# working.net
KiCad netlist of a schematic drawn in EAGLE
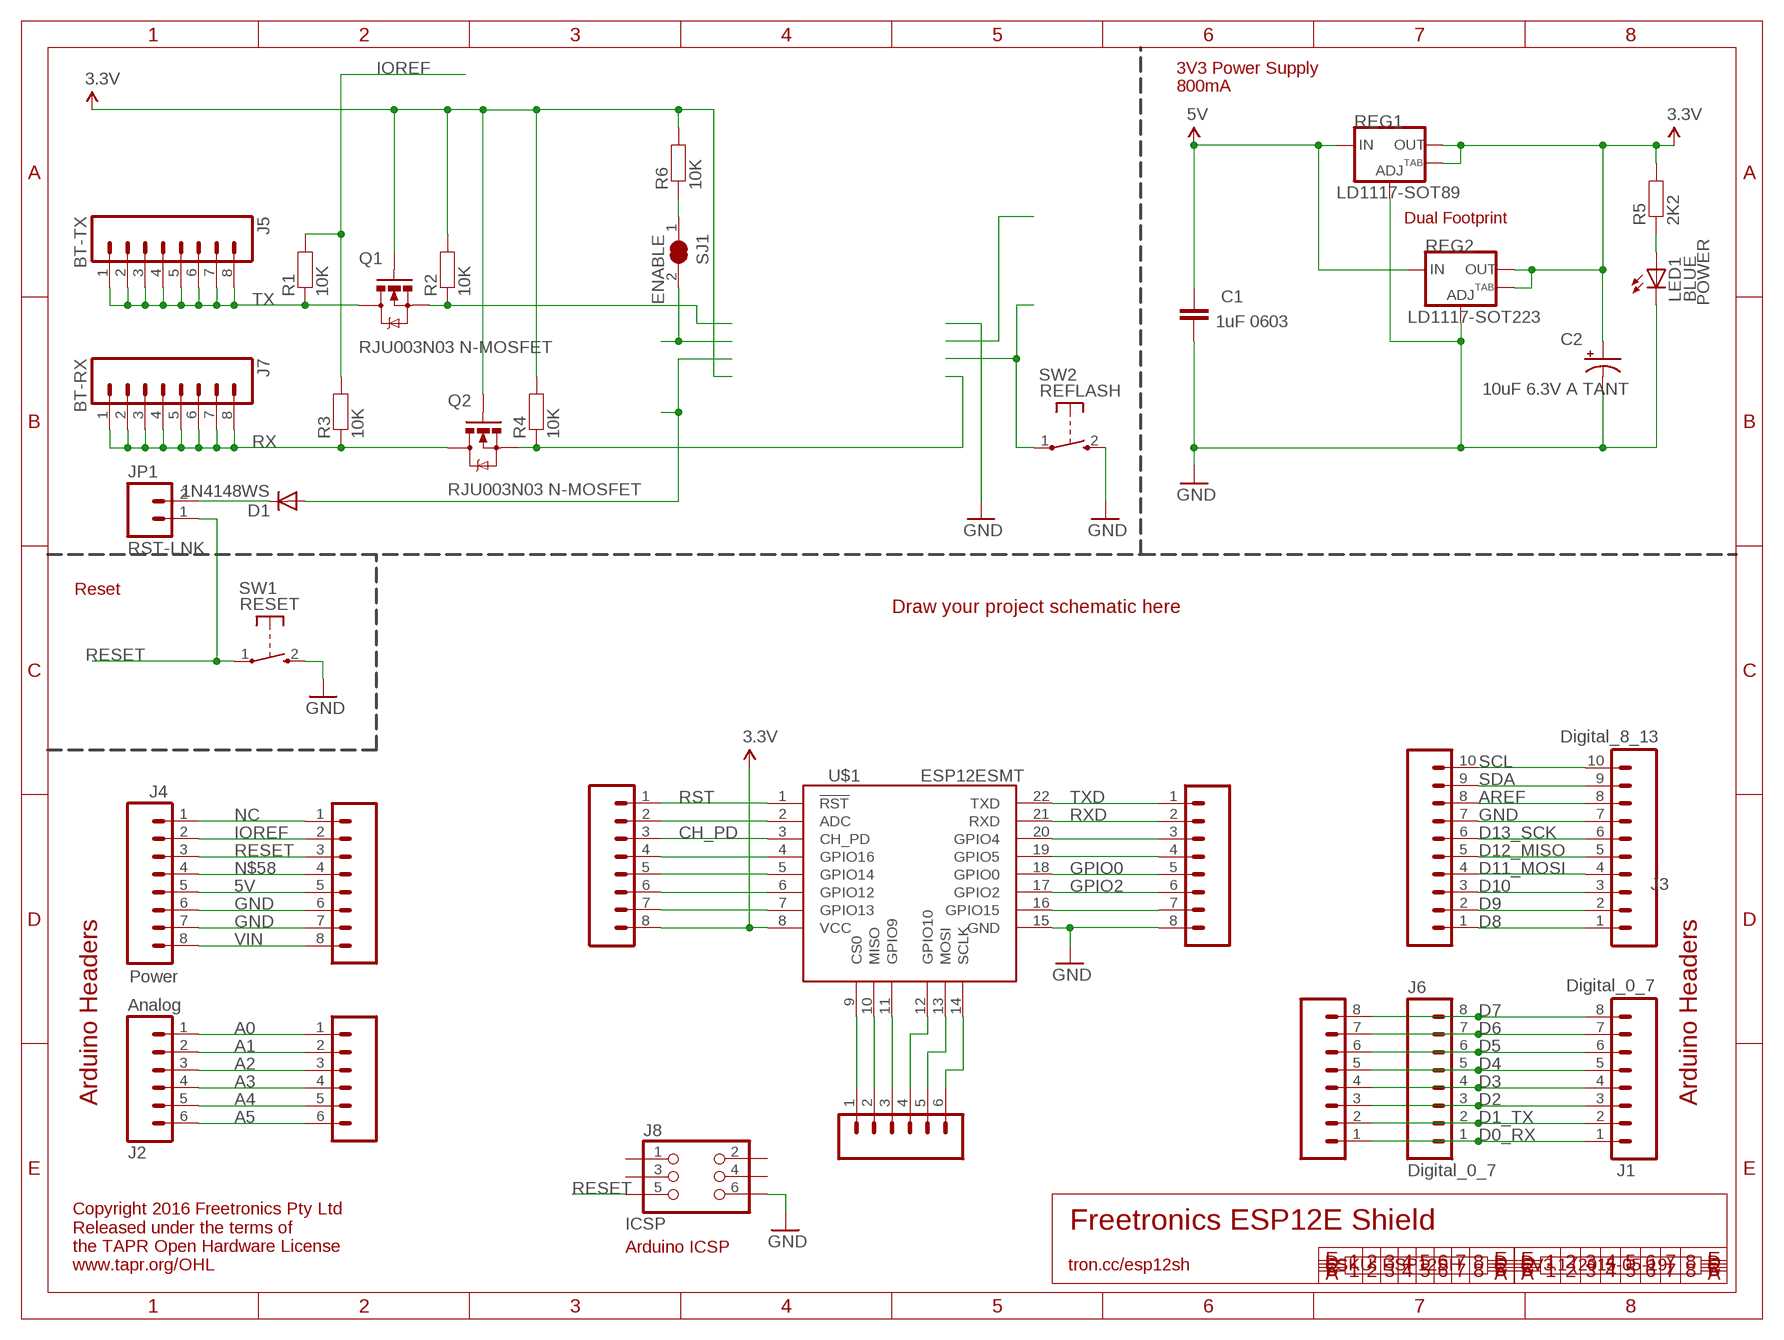
[diagram p0: schematic, sheet 1]

(export (version "E")
  (design (tool "Eeschema 10.0.6"))
  (components
    (comp (ref "C1")
      (value "1uF 0603")
      (footprint "eagle-import:0603")
      (libsource (lib "eagle-import") (part "CAP0603"))
    )
    (comp (ref "C2")
      (value "10uF 6.3V A TANT")
      (footprint "eagle-import:EIA3216")
      (libsource (lib "eagle-import") (part "CAP_POL1206"))
    )
    (comp (ref "D1")
      (value "1N4148WS")
      (footprint "eagle-import:SOD-323")
      (libsource (lib "eagle-import") (part "DIODESOD"))
    )
    (comp (ref "J1")
      (value "Digital_0_7")
      (footprint "eagle-import:1X08")
      (libsource (lib "eagle-import") (part "M08"))
    )
    (comp (ref "J2")
      (value "Analog")
      (footprint "eagle-import:1X06")
      (libsource (lib "eagle-import") (part "M06SIP"))
    )
    (comp (ref "J3")
      (value "Digital_8_13")
      (footprint "eagle-import:1X10")
      (libsource (lib "eagle-import") (part "M100.1"))
    )
    (comp (ref "J4")
      (value "Power")
      (footprint "eagle-import:1X08")
      (libsource (lib "eagle-import") (part "M08"))
    )
    (comp (ref "J5")
      (value "BT-TX")
      (footprint "eagle-import:1X08")
      (libsource (lib "eagle-import") (part "freetronics-original_M08"))
    )
    (comp (ref "J6")
      (value "Digital_0_7")
      (footprint "eagle-import:1X08")
      (libsource (lib "eagle-import") (part "freetronics-original_M08"))
    )
    (comp (ref "J7")
      (value "BT-RX")
      (footprint "eagle-import:1X08")
      (libsource (lib "eagle-import") (part "freetronics-original_M08"))
    )
    (comp (ref "J8")
      (value "ICSP")
      (footprint "eagle-import:2X03PTH")
      (libsource (lib "eagle-import") (part "ICSPPTH"))
    )
    (comp (ref "JP1")
      (value "RST-LNK")
      (footprint "eagle-import:1X02")
      (libsource (lib "eagle-import") (part "M02PTH"))
    )
    (comp (ref "LED1")
      (value "BLUE")
      (footprint "eagle-import:LED-0603")
      (libsource (lib "eagle-import") (part "LED0603"))
    )
    (comp (ref "Q1")
      (value "RJU003N03 N-MOSFET")
      (footprint "eagle-import:SOT32-3")
      (libsource (lib "eagle-import") (part "MOSFET-NSOT-323"))
    )
    (comp (ref "Q2")
      (value "RJU003N03 N-MOSFET")
      (footprint "eagle-import:SOT32-3")
      (libsource (lib "eagle-import") (part "MOSFET-NSOT-323"))
    )
    (comp (ref "R1")
      (value "10K")
      (footprint "eagle-import:0603")
      (libsource (lib "eagle-import") (part "RESISTOR0603"))
    )
    (comp (ref "R2")
      (value "10K")
      (footprint "eagle-import:0603")
      (libsource (lib "eagle-import") (part "RESISTOR0603"))
    )
    (comp (ref "R3")
      (value "10K")
      (footprint "eagle-import:0603")
      (libsource (lib "eagle-import") (part "RESISTOR0603"))
    )
    (comp (ref "R4")
      (value "10K")
      (footprint "eagle-import:0603")
      (libsource (lib "eagle-import") (part "RESISTOR0603"))
    )
    (comp (ref "R5")
      (value "2K2")
      (footprint "eagle-import:0603")
      (libsource (lib "eagle-import") (part "RESISTOR0603"))
    )
    (comp (ref "R6")
      (value "10K")
      (footprint "eagle-import:0603")
      (libsource (lib "eagle-import") (part "RESISTOR0603"))
    )
    (comp (ref "REG1")
      (value "LD1117-SOT89")
      (footprint "eagle-import:SOT89")
      (libsource (lib "eagle-import") (part "V_REG_LM1117SOT89"))
    )
    (comp (ref "REG2")
      (value "LD1117-SOT223")
      (footprint "eagle-import:SOT223")
      (libsource (lib "eagle-import") (part "V_REG_LM1117SOT223"))
    )
    (comp (ref "SJ1")
      (value "ENABLE")
      (footprint "eagle-import:SJC")
      (libsource (lib "eagle-import") (part "SJCN"))
    )
    (comp (ref "SL1")
      (value "Digital_0_7")
      (footprint "eagle-import:1X08")
      (libsource (lib "eagle-import") (part "M08"))
    )
    (comp (ref "SL2")
      (value "Analog")
      (footprint "eagle-import:1X06")
      (libsource (lib "eagle-import") (part "M06SIP"))
    )
    (comp (ref "SL3")
      (value "Digital_8_13")
      (footprint "eagle-import:1X10")
      (libsource (lib "eagle-import") (part "M100.1"))
    )
    (comp (ref "SL4")
      (value "Power")
      (footprint "eagle-import:1X08")
      (libsource (lib "eagle-import") (part "M08"))
    )
    (comp (ref "SL5")
      (value "5V")
      (footprint "eagle-import:1X08")
      (libsource (lib "eagle-import") (part "M08"))
    )
    (comp (ref "SL6")
      (value "5V")
      (footprint "eagle-import:1X08")
      (libsource (lib "eagle-import") (part "M08"))
    )
    (comp (ref "SL7")
      (value "Analog")
      (footprint "eagle-import:1X06")
      (libsource (lib "eagle-import") (part "M06SIP"))
    )
    (comp (ref "SW1")
      (value "RESET")
      (footprint "eagle-import:TACTILE_SWITCH_SMD_2PIN_TINY")
      (libsource (lib "eagle-import") (part "TAC_SWITCH_2PIN"))
    )
    (comp (ref "SW2")
      (value "REFLASH")
      (footprint "eagle-import:TACTILE_SWITCH_SMD_2PIN_TINY")
      (libsource (lib "eagle-import") (part "TAC_SWITCH_2PIN"))
    )
    (comp (ref "U$1")
      (value "ESP12ESMT")
      (footprint "eagle-import:ESP12E")
      (libsource (lib "eagle-import") (part "ESP12ESMT"))
    )
  )
  (nets
    (net (code "1") (name "/A0") (class "Default")
      (node (ref "J2") (pin "1") (pinfunction "1_1") (pintype "passive"))
      (node (ref "SL2") (pin "1") (pinfunction "1_1") (pintype "passive"))
    )
    (net (code "2") (name "/A1") (class "Default")
      (node (ref "J2") (pin "2") (pinfunction "2_2") (pintype "passive"))
      (node (ref "SL2") (pin "2") (pinfunction "2_2") (pintype "passive"))
    )
    (net (code "3") (name "/A2") (class "Default")
      (node (ref "J2") (pin "3") (pinfunction "3_3") (pintype "passive"))
      (node (ref "SL2") (pin "3") (pinfunction "3_3") (pintype "passive"))
    )
    (net (code "4") (name "/A3") (class "Default")
      (node (ref "J2") (pin "4") (pinfunction "4_4") (pintype "passive"))
      (node (ref "SL2") (pin "4") (pinfunction "4_4") (pintype "passive"))
    )
    (net (code "5") (name "/A4") (class "Default")
      (node (ref "J2") (pin "5") (pinfunction "5_5") (pintype "passive"))
      (node (ref "SL2") (pin "5") (pinfunction "5_5") (pintype "passive"))
    )
    (net (code "6") (name "/A5") (class "Default")
      (node (ref "J2") (pin "6") (pinfunction "6_6") (pintype "passive"))
      (node (ref "SL2") (pin "6") (pinfunction "6_6") (pintype "passive"))
    )
    (net (code "7") (name "/AREF") (class "Default")
      (node (ref "J3") (pin "8") (pinfunction "8_8") (pintype "passive"))
      (node (ref "SL3") (pin "8") (pinfunction "8_8") (pintype "passive"))
    )
    (net (code "8") (name "/CH_PD") (class "Default")
      (node (ref "SJ1") (pin "2") (pinfunction "2_2") (pintype "passive"))
      (node (ref "SL6") (pin "3") (pinfunction "3_3") (pintype "passive"))
      (node (ref "U$1") (pin "3") (pinfunction "CH_PD_3") (pintype "input"))
    )
    (net (code "9") (name "/D0_RX") (class "Default")
      (node (ref "J1") (pin "1") (pinfunction "1_1") (pintype "passive"))
      (node (ref "J6") (pin "1") (pinfunction "1_1") (pintype "passive"))
      (node (ref "SL1") (pin "1") (pinfunction "1_1") (pintype "passive"))
    )
    (net (code "10") (name "/D1_TX") (class "Default")
      (node (ref "J1") (pin "2") (pinfunction "2_2") (pintype "passive"))
      (node (ref "J6") (pin "2") (pinfunction "2_2") (pintype "passive"))
      (node (ref "SL1") (pin "2") (pinfunction "2_2") (pintype "passive"))
    )
    (net (code "11") (name "/D2") (class "Default")
      (node (ref "J1") (pin "3") (pinfunction "3_3") (pintype "passive"))
      (node (ref "J6") (pin "3") (pinfunction "3_3") (pintype "passive"))
      (node (ref "SL1") (pin "3") (pinfunction "3_3") (pintype "passive"))
    )
    (net (code "12") (name "/D3") (class "Default")
      (node (ref "J1") (pin "4") (pinfunction "4_4") (pintype "passive"))
      (node (ref "J6") (pin "4") (pinfunction "4_4") (pintype "passive"))
      (node (ref "SL1") (pin "4") (pinfunction "4_4") (pintype "passive"))
    )
    (net (code "13") (name "/D4") (class "Default")
      (node (ref "J1") (pin "5") (pinfunction "5_5") (pintype "passive"))
      (node (ref "J6") (pin "5") (pinfunction "5_5") (pintype "passive"))
      (node (ref "SL1") (pin "5") (pinfunction "5_5") (pintype "passive"))
    )
    (net (code "14") (name "/D5") (class "Default")
      (node (ref "J1") (pin "6") (pinfunction "6_6") (pintype "passive"))
      (node (ref "J6") (pin "6") (pinfunction "6_6") (pintype "passive"))
      (node (ref "SL1") (pin "6") (pinfunction "6_6") (pintype "passive"))
    )
    (net (code "15") (name "/D6") (class "Default")
      (node (ref "J1") (pin "7") (pinfunction "7_7") (pintype "passive"))
      (node (ref "J6") (pin "7") (pinfunction "7_7") (pintype "passive"))
      (node (ref "SL1") (pin "7") (pinfunction "7_7") (pintype "passive"))
    )
    (net (code "16") (name "/D7") (class "Default")
      (node (ref "J1") (pin "8") (pinfunction "8_8") (pintype "passive"))
      (node (ref "J6") (pin "8") (pinfunction "8_8") (pintype "passive"))
      (node (ref "SL1") (pin "8") (pinfunction "8_8") (pintype "passive"))
    )
    (net (code "17") (name "/D8") (class "Default")
      (node (ref "J3") (pin "1") (pinfunction "1_1") (pintype "passive"))
      (node (ref "SL3") (pin "1") (pinfunction "1_1") (pintype "passive"))
    )
    (net (code "18") (name "/D9") (class "Default")
      (node (ref "J3") (pin "2") (pinfunction "2_2") (pintype "passive"))
      (node (ref "SL3") (pin "2") (pinfunction "2_2") (pintype "passive"))
    )
    (net (code "19") (name "/D10") (class "Default")
      (node (ref "J3") (pin "3") (pinfunction "3_3") (pintype "passive"))
      (node (ref "SL3") (pin "3") (pinfunction "3_3") (pintype "passive"))
    )
    (net (code "20") (name "/D11_MOSI") (class "Default")
      (node (ref "J3") (pin "4") (pinfunction "4_4") (pintype "passive"))
      (node (ref "SL3") (pin "4") (pinfunction "4_4") (pintype "passive"))
    )
    (net (code "21") (name "/D12_MISO") (class "Default")
      (node (ref "J3") (pin "5") (pinfunction "5_5") (pintype "passive"))
      (node (ref "SL3") (pin "5") (pinfunction "5_5") (pintype "passive"))
    )
    (net (code "22") (name "/D13_SCK") (class "Default")
      (node (ref "J3") (pin "6") (pinfunction "6_6") (pintype "passive"))
      (node (ref "SL3") (pin "6") (pinfunction "6_6") (pintype "passive"))
    )
    (net (code "23") (name "/GPIO0") (class "Default")
      (node (ref "SL5") (pin "5") (pinfunction "5_5") (pintype "passive"))
      (node (ref "SW2") (pin "1") (pinfunction "P_1") (pintype "passive"))
      (node (ref "U$1") (pin "18") (pinfunction "GPIO0_18") (pintype "bidirectional"))
    )
    (net (code "24") (name "/GPIO2") (class "Default")
      (node (ref "SL5") (pin "6") (pinfunction "6_6") (pintype "passive"))
      (node (ref "U$1") (pin "17") (pinfunction "GPIO2_17") (pintype "bidirectional"))
    )
    (net (code "25") (name "/IOREF") (class "Default")
      (node (ref "J4") (pin "2") (pinfunction "2_2") (pintype "passive"))
      (node (ref "R1") (pin "2") (pinfunction "2_2") (pintype "passive"))
      (node (ref "R3") (pin "2") (pinfunction "2_2") (pintype "passive"))
      (node (ref "SL4") (pin "2") (pinfunction "2_2") (pintype "passive"))
    )
    (net (code "26") (name "/N$58") (class "Default")
      (node (ref "J4") (pin "4") (pinfunction "4_4") (pintype "passive"))
      (node (ref "SL4") (pin "4") (pinfunction "4_4") (pintype "passive"))
    )
    (net (code "27") (name "/NC") (class "Default")
      (node (ref "J4") (pin "1") (pinfunction "1_1") (pintype "passive"))
      (node (ref "SL4") (pin "1") (pinfunction "1_1") (pintype "passive"))
    )
    (net (code "28") (name "/RESET") (class "Default")
      (node (ref "J4") (pin "3") (pinfunction "3_3") (pintype "passive"))
      (node (ref "J8") (pin "5") (pinfunction "5_5") (pintype "passive"))
      (node (ref "JP1") (pin "1") (pinfunction "1_1") (pintype "passive"))
      (node (ref "SL4") (pin "3") (pinfunction "3_3") (pintype "passive"))
      (node (ref "SW1") (pin "1") (pinfunction "P_1") (pintype "passive"))
    )
    (net (code "29") (name "/RST") (class "Default")
      (node (ref "D1") (pin "2") (pinfunction "A_2") (pintype "passive"))
      (node (ref "SL6") (pin "1") (pinfunction "1_1") (pintype "passive"))
      (node (ref "U$1") (pin "1") (pinfunction "~{RST}_1") (pintype "bidirectional"))
    )
    (net (code "30") (name "/RX") (class "Default")
      (node (ref "J7") (pin "1") (pinfunction "1_1") (pintype "passive"))
      (node (ref "J7") (pin "2") (pinfunction "2_2") (pintype "passive"))
      (node (ref "J7") (pin "3") (pinfunction "3_3") (pintype "passive"))
      (node (ref "J7") (pin "4") (pinfunction "4_4") (pintype "passive"))
      (node (ref "J7") (pin "5") (pinfunction "5_5") (pintype "passive"))
      (node (ref "J7") (pin "6") (pinfunction "6_6") (pintype "passive"))
      (node (ref "J7") (pin "7") (pinfunction "7_7") (pintype "passive"))
      (node (ref "J7") (pin "8") (pinfunction "8_8") (pintype "passive"))
      (node (ref "Q2") (pin "3") (pinfunction "D_3") (pintype "passive"))
      (node (ref "R3") (pin "1") (pinfunction "1_1") (pintype "passive"))
    )
    (net (code "31") (name "/RXD") (class "Default")
      (node (ref "Q2") (pin "2") (pinfunction "S_2") (pintype "passive"))
      (node (ref "R4") (pin "1") (pinfunction "1_1") (pintype "passive"))
      (node (ref "SL5") (pin "2") (pinfunction "2_2") (pintype "passive"))
      (node (ref "U$1") (pin "21") (pinfunction "RXD_21") (pintype "input"))
    )
    (net (code "32") (name "/SCL") (class "Default")
      (node (ref "J3") (pin "10") (pinfunction "10_10") (pintype "passive"))
      (node (ref "SL3") (pin "10") (pinfunction "10_10") (pintype "passive"))
    )
    (net (code "33") (name "/SDA") (class "Default")
      (node (ref "J3") (pin "9") (pinfunction "9_9") (pintype "passive"))
      (node (ref "SL3") (pin "9") (pinfunction "9_9") (pintype "passive"))
    )
    (net (code "34") (name "/TX") (class "Default")
      (node (ref "J5") (pin "1") (pinfunction "1_1") (pintype "passive"))
      (node (ref "J5") (pin "2") (pinfunction "2_2") (pintype "passive"))
      (node (ref "J5") (pin "3") (pinfunction "3_3") (pintype "passive"))
      (node (ref "J5") (pin "4") (pinfunction "4_4") (pintype "passive"))
      (node (ref "J5") (pin "5") (pinfunction "5_5") (pintype "passive"))
      (node (ref "J5") (pin "6") (pinfunction "6_6") (pintype "passive"))
      (node (ref "J5") (pin "7") (pinfunction "7_7") (pintype "passive"))
      (node (ref "J5") (pin "8") (pinfunction "8_8") (pintype "passive"))
      (node (ref "Q1") (pin "3") (pinfunction "D_3") (pintype "passive"))
      (node (ref "R1") (pin "1") (pinfunction "1_1") (pintype "passive"))
    )
    (net (code "35") (name "/TXD") (class "Default")
      (node (ref "Q1") (pin "2") (pinfunction "S_2") (pintype "passive"))
      (node (ref "R2") (pin "1") (pinfunction "1_1") (pintype "passive"))
      (node (ref "SL5") (pin "1") (pinfunction "1_1") (pintype "passive"))
      (node (ref "U$1") (pin "22") (pinfunction "TXD_22") (pintype "output"))
    )
    (net (code "36") (name "/VIN") (class "Default")
      (node (ref "J4") (pin "8") (pinfunction "8_8") (pintype "passive"))
      (node (ref "SL4") (pin "8") (pinfunction "8_8") (pintype "passive"))
    )
    (net (code "37") (name "3.3V") (class "Default")
      (node (ref "C2") (pin "A") (pinfunction "+_A") (pintype "passive"))
      (node (ref "Q1") (pin "1") (pinfunction "G_1") (pintype "passive"))
      (node (ref "Q2") (pin "1") (pinfunction "G_1") (pintype "passive"))
      (node (ref "R2") (pin "2") (pinfunction "2_2") (pintype "passive"))
      (node (ref "R4") (pin "2") (pinfunction "2_2") (pintype "passive"))
      (node (ref "R5") (pin "2") (pinfunction "2_2") (pintype "passive"))
      (node (ref "R6") (pin "2") (pinfunction "2_2") (pintype "passive"))
      (node (ref "REG1") (pin "2") (pinfunction "OUT_2") (pintype "output"))
      (node (ref "REG1") (pin "4") (pinfunction "OUT_4") (pintype "output"))
      (node (ref "REG2") (pin "2") (pinfunction "OUT_2") (pintype "output"))
      (node (ref "REG2") (pin "4") (pinfunction "OUT_4") (pintype "output"))
      (node (ref "SL6") (pin "8") (pinfunction "8_8") (pintype "passive"))
      (node (ref "U$1") (pin "8") (pinfunction "VCC_8") (pintype "power_in"))
    )
    (net (code "38") (name "5V") (class "Default")
      (node (ref "C1") (pin "1") (pinfunction "1_1") (pintype "passive"))
      (node (ref "J4") (pin "5") (pinfunction "5_5") (pintype "passive"))
      (node (ref "REG1") (pin "3") (pinfunction "IN_3") (pintype "input"))
      (node (ref "REG2") (pin "3") (pinfunction "IN_3") (pintype "input"))
      (node (ref "SL4") (pin "5") (pinfunction "5_5") (pintype "passive"))
    )
    (net (code "39") (name "GND") (class "Default")
      (node (ref "C1") (pin "2") (pinfunction "2_2") (pintype "passive"))
      (node (ref "C2") (pin "C") (pinfunction "-_C") (pintype "passive"))
      (node (ref "J3") (pin "7") (pinfunction "7_7") (pintype "passive"))
      (node (ref "J4") (pin "6") (pinfunction "6_6") (pintype "passive"))
      (node (ref "J4") (pin "7") (pinfunction "7_7") (pintype "passive"))
      (node (ref "J8") (pin "6") (pinfunction "6_6") (pintype "passive"))
      (node (ref "LED1") (pin "C") (pinfunction "C_C") (pintype "passive"))
      (node (ref "REG1") (pin "1") (pinfunction "ADJ_1") (pintype "input"))
      (node (ref "REG2") (pin "1") (pinfunction "ADJ_1") (pintype "input"))
      (node (ref "SL3") (pin "7") (pinfunction "7_7") (pintype "passive"))
      (node (ref "SL4") (pin "6") (pinfunction "6_6") (pintype "passive"))
      (node (ref "SL4") (pin "7") (pinfunction "7_7") (pintype "passive"))
      (node (ref "SL5") (pin "8") (pinfunction "8_8") (pintype "passive"))
      (node (ref "SW1") (pin "2") (pinfunction "S_2") (pintype "passive"))
      (node (ref "SW2") (pin "2") (pinfunction "S_2") (pintype "passive"))
      (node (ref "U$1") (pin "15") (pinfunction "GND_15") (pintype "power_in"))
    )
    (net (code "40") (name "Net-(D1-C)") (class "Default")
      (node (ref "D1") (pin "1") (pinfunction "C_1") (pintype "passive"))
      (node (ref "JP1") (pin "2") (pinfunction "2_2") (pintype "passive"))
    )
    (net (code "41") (name "Net-(LED1-PadA)") (class "Default")
      (node (ref "LED1") (pin "A") (pinfunction "A_A") (pintype "passive"))
      (node (ref "R5") (pin "1") (pinfunction "1_1") (pintype "passive"))
    )
    (net (code "42") (name "Net-(R6-Pad1)") (class "Default")
      (node (ref "R6") (pin "1") (pinfunction "1_1") (pintype "passive"))
      (node (ref "SJ1") (pin "1") (pinfunction "1_1") (pintype "passive"))
    )
    (net (code "43") (name "Net-(U$1-ADC)") (class "Default")
      (node (ref "SL6") (pin "2") (pinfunction "2_2") (pintype "passive"))
      (node (ref "U$1") (pin "2") (pinfunction "ADC_2") (pintype "input"))
    )
    (net (code "44") (name "Net-(U$1-CS0)") (class "Default")
      (node (ref "SL7") (pin "1") (pinfunction "1_1") (pintype "passive"))
      (node (ref "U$1") (pin "9") (pinfunction "CS0_9") (pintype "bidirectional"))
    )
    (net (code "45") (name "Net-(U$1-GPIO4)") (class "Default")
      (node (ref "SL5") (pin "3") (pinfunction "3_3") (pintype "passive"))
      (node (ref "U$1") (pin "20") (pinfunction "GPIO4_20") (pintype "bidirectional"))
    )
    (net (code "46") (name "Net-(U$1-GPIO5)") (class "Default")
      (node (ref "SL5") (pin "4") (pinfunction "4_4") (pintype "passive"))
      (node (ref "U$1") (pin "19") (pinfunction "GPIO5_19") (pintype "bidirectional"))
    )
    (net (code "47") (name "Net-(U$1-GPIO9)") (class "Default")
      (node (ref "SL7") (pin "3") (pinfunction "3_3") (pintype "passive"))
      (node (ref "U$1") (pin "11") (pinfunction "GPIO9_11") (pintype "bidirectional"))
    )
    (net (code "48") (name "Net-(U$1-GPIO10)") (class "Default")
      (node (ref "SL7") (pin "4") (pinfunction "4_4") (pintype "passive"))
      (node (ref "U$1") (pin "12") (pinfunction "GPIO10_12") (pintype "bidirectional"))
    )
    (net (code "49") (name "Net-(U$1-GPIO12)") (class "Default")
      (node (ref "SL6") (pin "6") (pinfunction "6_6") (pintype "passive"))
      (node (ref "U$1") (pin "6") (pinfunction "GPIO12_6") (pintype "bidirectional"))
    )
    (net (code "50") (name "Net-(U$1-GPIO13)") (class "Default")
      (node (ref "SL6") (pin "7") (pinfunction "7_7") (pintype "passive"))
      (node (ref "U$1") (pin "7") (pinfunction "GPIO13_7") (pintype "bidirectional"))
    )
    (net (code "51") (name "Net-(U$1-GPIO14)") (class "Default")
      (node (ref "SL6") (pin "5") (pinfunction "5_5") (pintype "passive"))
      (node (ref "U$1") (pin "5") (pinfunction "GPIO14_5") (pintype "bidirectional"))
    )
    (net (code "52") (name "Net-(U$1-GPIO15)") (class "Default")
      (node (ref "SL5") (pin "7") (pinfunction "7_7") (pintype "passive"))
      (node (ref "U$1") (pin "16") (pinfunction "GPIO15_16") (pintype "bidirectional"))
    )
    (net (code "53") (name "Net-(U$1-GPIO16)") (class "Default")
      (node (ref "SL6") (pin "4") (pinfunction "4_4") (pintype "passive"))
      (node (ref "U$1") (pin "4") (pinfunction "GPIO16_4") (pintype "bidirectional"))
    )
    (net (code "54") (name "Net-(U$1-MISO)") (class "Default")
      (node (ref "SL7") (pin "2") (pinfunction "2_2") (pintype "passive"))
      (node (ref "U$1") (pin "10") (pinfunction "MISO_10") (pintype "bidirectional"))
    )
    (net (code "55") (name "Net-(U$1-MOSI)") (class "Default")
      (node (ref "SL7") (pin "5") (pinfunction "5_5") (pintype "passive"))
      (node (ref "U$1") (pin "13") (pinfunction "MOSI_13") (pintype "bidirectional"))
    )
    (net (code "56") (name "Net-(U$1-SCLK)") (class "Default")
      (node (ref "SL7") (pin "6") (pinfunction "6_6") (pintype "passive"))
      (node (ref "U$1") (pin "14") (pinfunction "SCLK_14") (pintype "bidirectional"))
    )
    (net (code "57") (name "unconnected-(J8-Pad1)") (class "Default")
      (node (ref "J8") (pin "1") (pinfunction "1_1") (pintype "passive"))
    )
    (net (code "58") (name "unconnected-(J8-Pad2)") (class "Default")
      (node (ref "J8") (pin "2") (pinfunction "2_2") (pintype "passive"))
    )
    (net (code "59") (name "unconnected-(J8-Pad3)") (class "Default")
      (node (ref "J8") (pin "3") (pinfunction "3_3") (pintype "passive"))
    )
    (net (code "60") (name "unconnected-(J8-Pad4)") (class "Default")
      (node (ref "J8") (pin "4") (pinfunction "4_4") (pintype "passive"))
    )
  )
)
